# LEO_COTS_rev0.net
KiCad netlist of a schematic drawn in Altium Designer
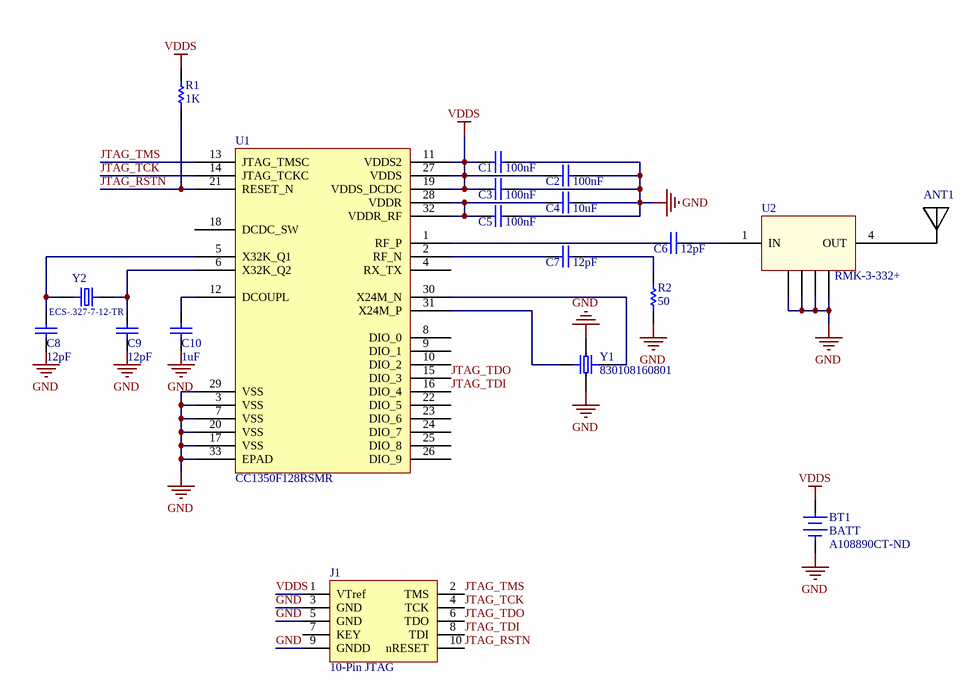
[diagram p0: LEO_COTS_rev0.SchDoc]

(export (version "E")
  (design (tool "Eeschema 10.0.6"))
  (components
    (comp (ref "ANT1") (value "ANT") (libsource (lib "LEO_COTS_components") (part "ANT")))
    (comp (ref "BT1")
      (value "BATT")
      (footprint "1318164-1")
      (fields (field (name "SUPPLIER PART NUMBER 1") "A108890CT-ND"))
      (libsource (lib "LEO_COTS_components") (part "BATT"))
    )
    (comp (ref "C1")
      (value "100nF")
      (footprint "CAPC0603X04N")
      (description "CAP CER 0201")
      (fields (field (name "Comment") "CAP_0201"))
      (libsource (lib "LEO_COTS_components") (part "CAP_0201"))
    )
    (comp (ref "C2")
      (value "100nF")
      (footprint "CAPC0603X04N")
      (description "CAP CER 0201")
      (fields (field (name "Comment") "CAP_0201"))
      (libsource (lib "LEO_COTS_components") (part "CAP_0201"))
    )
    (comp (ref "C3")
      (value "100nF")
      (footprint "CAPC0603X04N")
      (description "CAP CER 0201")
      (fields (field (name "Comment") "CAP_0201"))
      (libsource (lib "LEO_COTS_components") (part "CAP_0201"))
    )
    (comp (ref "C4")
      (value "10uF")
      (footprint "CAPC1608X05N")
      (description "CAP CER 0603")
      (fields (field (name "Comment") "CAP_0603"))
      (libsource (lib "LEO_COTS_components") (part "CAP_0603"))
    )
    (comp (ref "C5")
      (value "100nF")
      (footprint "CAPC0603X04N")
      (description "CAP CER 0201")
      (fields (field (name "Comment") "CAP_0201"))
      (libsource (lib "LEO_COTS_components") (part "CAP_0201"))
    )
    (comp (ref "C6")
      (value "12pF")
      (footprint "CAPC0603X04N")
      (description "CAP CER 0201")
      (fields (field (name "Comment") "CAP_0201"))
      (libsource (lib "LEO_COTS_components") (part "CAP_0201"))
    )
    (comp (ref "C7")
      (value "12pF")
      (footprint "CAPC0603X04N")
      (description "CAP CER 0201")
      (fields (field (name "Comment") "CAP_0201"))
      (libsource (lib "LEO_COTS_components") (part "CAP_0201"))
    )
    (comp (ref "C8")
      (value "12pF")
      (footprint "CAPC0603X04N")
      (description "CAP CER 0201")
      (fields (field (name "Comment") "CAP_0201"))
      (libsource (lib "LEO_COTS_components") (part "CAP_0201"))
    )
    (comp (ref "C9")
      (value "12pF")
      (footprint "CAPC0603X04N")
      (description "CAP CER 0201")
      (fields (field (name "Comment") "CAP_0201"))
      (libsource (lib "LEO_COTS_components") (part "CAP_0201"))
    )
    (comp (ref "C10")
      (value "1uF")
      (footprint "CAPC0603X04N")
      (description "CAP CER 0201")
      (fields (field (name "Comment") "CAP_0201"))
      (libsource (lib "LEO_COTS_components") (part "CAP_0201"))
    )
    (comp (ref "J1")
      (value "10-Pin JTAG")
      (footprint "FTSH-105-01-F-DV-007-K")
      (libsource (lib "LEO_COTS_components") (part "CM10"))
    )
    (comp (ref "R1")
      (value "1K")
      (footprint "CAPC0603X04N")
      (description "Semiconductor Resistor")
      (fields (field (name "Comment") "Res Semi") (field (name "PUBLISHER") "Altium Limited"))
      (libsource (lib "LEO_COTS_components") (part "Res Semi"))
    )
    (comp (ref "R2")
      (value "50")
      (footprint "CAPC0603X04N")
      (description "Semiconductor Resistor")
      (fields (field (name "Comment") "Res Semi") (field (name "PUBLISHER") "Altium Limited"))
      (libsource (lib "LEO_COTS_components") (part "Res Semi"))
    )
    (comp (ref "U1")
      (value "CC1350F128RSMR")
      (footprint "QFN40P400X400X100-33N")
      (description "Ultra-Low-Power Dual-Band Wireless MCU")
      (libsource (lib "LEO_COTS_components") (part "CC1350F128RSMR"))
    )
    (comp (ref "U2")
      (value "RMK-3-332+")
      (footprint "RMK-3-331+")
      (description "3x Frequency Multiplier")
      (libsource (lib "LEO_COTS_components") (part "RMK-3-332+"))
    )
    (comp (ref "Y1")
      (value "830108160801")
      (footprint "LFXTAL081608")
      (description "24 MHz crystal")
      (fields (field (name "MP") "ECS-.327-7-12-TR"))
      (libsource (lib "LEO_COTS_components") (part "830108160801"))
    )
    (comp (ref "Y2")
      (value "ECS-.327-7-12-TR")
      (footprint "XTAL_ECS-.327-7-12-TR")
      (description "32.768 kHz SMD Crystal")
      (libsource (lib "LEO_COTS_components") (part "ECS-.327-7-12-TR"))
    )
  )
  (nets
    (net (code "1") (name "/JTAG_RSTN") (class "Default")
      (node (ref "J1") (pin "10") (pinfunction "nRESET_10") (pintype "passive"))
      (node (ref "R1") (pin "1") (pinfunction "1_1") (pintype "passive"))
      (node (ref "U1") (pin "21") (pinfunction "RESET_N_21") (pintype "passive"))
    )
    (net (code "2") (name "/JTAG_TCK") (class "Default")
      (node (ref "J1") (pin "4") (pinfunction "TCK_4") (pintype "passive"))
      (node (ref "U1") (pin "14") (pinfunction "JTAG_TCKC_14") (pintype "passive"))
    )
    (net (code "3") (name "/JTAG_TDI") (class "Default")
      (node (ref "J1") (pin "8") (pinfunction "TDI_8") (pintype "passive"))
      (node (ref "U1") (pin "16") (pinfunction "DIO_4_16") (pintype "passive"))
    )
    (net (code "4") (name "/JTAG_TDO") (class "Default")
      (node (ref "J1") (pin "6") (pinfunction "TDO_6") (pintype "passive"))
      (node (ref "U1") (pin "15") (pinfunction "DIO_3_15") (pintype "passive"))
    )
    (net (code "5") (name "/JTAG_TMS") (class "Default")
      (node (ref "J1") (pin "2") (pinfunction "TMS_2") (pintype "passive"))
      (node (ref "U1") (pin "13") (pinfunction "JTAG_TMSC_13") (pintype "passive"))
    )
    (net (code "6") (name "GND") (class "Default")
      (node (ref "BT1") (pin "2") (pinfunction "-_2") (pintype "passive"))
      (node (ref "C1") (pin "1") (pinfunction "1_1") (pintype "passive"))
      (node (ref "C10") (pin "1") (pinfunction "1_1") (pintype "passive"))
      (node (ref "C2") (pin "1") (pinfunction "1_1") (pintype "passive"))
      (node (ref "C3") (pin "1") (pinfunction "1_1") (pintype "passive"))
      (node (ref "C4") (pin "2") (pinfunction "2_2") (pintype "passive"))
      (node (ref "C5") (pin "1") (pinfunction "1_1") (pintype "passive"))
      (node (ref "C8") (pin "1") (pinfunction "1_1") (pintype "passive"))
      (node (ref "C9") (pin "1") (pinfunction "1_1") (pintype "passive"))
      (node (ref "J1") (pin "3") (pinfunction "GND_3") (pintype "passive"))
      (node (ref "J1") (pin "5") (pinfunction "GND_5") (pintype "passive"))
      (node (ref "J1") (pin "9") (pinfunction "GNDD_9") (pintype "passive"))
      (node (ref "R2") (pin "1") (pinfunction "1_1") (pintype "passive"))
      (node (ref "U1") (pin "17") (pinfunction "VSS_17") (pintype "passive"))
      (node (ref "U1") (pin "20") (pinfunction "VSS_20") (pintype "passive"))
      (node (ref "U1") (pin "29") (pinfunction "VSS_29") (pintype "passive"))
      (node (ref "U1") (pin "3") (pinfunction "VSS_3") (pintype "passive"))
      (node (ref "U1") (pin "33") (pinfunction "EPAD_33") (pintype "passive"))
      (node (ref "U1") (pin "7") (pinfunction "VSS_7") (pintype "passive"))
      (node (ref "U2") (pin "2") (pinfunction "2_2") (pintype "passive"))
      (node (ref "U2") (pin "3") (pinfunction "3_3") (pintype "passive"))
      (node (ref "U2") (pin "5") (pinfunction "5_5") (pintype "passive"))
      (node (ref "U2") (pin "6") (pinfunction "6_6") (pintype "passive"))
      (node (ref "Y1") (pin "2") (pinfunction "2_2") (pintype "passive"))
      (node (ref "Y1") (pin "4") (pinfunction "4_4") (pintype "passive"))
    )
    (net (code "7") (name "Net-(C7-Pad1)") (class "Default")
      (node (ref "C7") (pin "1") (pinfunction "1_1") (pintype "passive"))
      (node (ref "R2") (pin "2") (pinfunction "2_2") (pintype "passive"))
    )
    (net (code "8") (name "Net-(U1-DCOUPL)") (class "Default")
      (node (ref "C10") (pin "2") (pinfunction "2_2") (pintype "passive"))
      (node (ref "U1") (pin "12") (pinfunction "DCOUPL_12") (pintype "passive"))
    )
    (net (code "9") (name "Net-(U1-RF_N)") (class "Default")
      (node (ref "C7") (pin "2") (pinfunction "2_2") (pintype "passive"))
      (node (ref "U1") (pin "2") (pinfunction "RF_N_2") (pintype "passive"))
    )
    (net (code "10") (name "Net-(U1-RF_P)") (class "Default")
      (node (ref "C6") (pin "2") (pinfunction "2_2") (pintype "passive"))
      (node (ref "U1") (pin "1") (pinfunction "RF_P_1") (pintype "passive"))
    )
    (net (code "11") (name "Net-(U1-VDDR)") (class "Default")
      (node (ref "C4") (pin "1") (pinfunction "1_1") (pintype "passive"))
      (node (ref "C5") (pin "2") (pinfunction "2_2") (pintype "passive"))
      (node (ref "U1") (pin "28") (pinfunction "VDDR_28") (pintype "passive"))
      (node (ref "U1") (pin "32") (pinfunction "VDDR_RF_32") (pintype "passive"))
    )
    (net (code "12") (name "Net-(U1-X24M_N)") (class "Default")
      (node (ref "U1") (pin "30") (pinfunction "X24M_N_30") (pintype "passive"))
      (node (ref "Y1") (pin "3") (pinfunction "3_3") (pintype "passive"))
    )
    (net (code "13") (name "Net-(U1-X24M_P)") (class "Default")
      (node (ref "U1") (pin "31") (pinfunction "X24M_P_31") (pintype "passive"))
      (node (ref "Y1") (pin "1") (pinfunction "1_1") (pintype "passive"))
    )
    (net (code "14") (name "Net-(U1-X32K_Q1)") (class "Default")
      (node (ref "C8") (pin "2") (pinfunction "2_2") (pintype "passive"))
      (node (ref "U1") (pin "5") (pinfunction "X32K_Q1_5") (pintype "passive"))
      (node (ref "Y2") (pin "1") (pinfunction "1_1") (pintype "passive"))
    )
    (net (code "15") (name "Net-(U1-X32K_Q2)") (class "Default")
      (node (ref "C9") (pin "2") (pinfunction "2_2") (pintype "passive"))
      (node (ref "U1") (pin "6") (pinfunction "X32K_Q2_6") (pintype "passive"))
      (node (ref "Y2") (pin "2") (pinfunction "2_2") (pintype "passive"))
    )
    (net (code "16") (name "Net-(U2-IN)") (class "Default")
      (node (ref "C6") (pin "1") (pinfunction "1_1") (pintype "passive"))
      (node (ref "U2") (pin "1") (pinfunction "IN_1") (pintype "passive"))
    )
    (net (code "17") (name "VDDS") (class "Default")
      (node (ref "BT1") (pin "1") (pinfunction "+_1") (pintype "passive"))
      (node (ref "C1") (pin "2") (pinfunction "2_2") (pintype "passive"))
      (node (ref "C2") (pin "2") (pinfunction "2_2") (pintype "passive"))
      (node (ref "C3") (pin "2") (pinfunction "2_2") (pintype "passive"))
      (node (ref "J1") (pin "1") (pinfunction "VTref_1") (pintype "passive"))
      (node (ref "R1") (pin "2") (pinfunction "2_2") (pintype "passive"))
      (node (ref "U1") (pin "11") (pinfunction "VDDS2_11") (pintype "passive"))
      (node (ref "U1") (pin "19") (pinfunction "VDDS_DCDC_19") (pintype "passive"))
      (node (ref "U1") (pin "27") (pinfunction "VDDS_27") (pintype "passive"))
    )
    (net (code "18") (name "unconnected-(J1-KEY-Pad7)") (class "Default")
      (node (ref "J1") (pin "7") (pinfunction "KEY_7") (pintype "passive"))
    )
    (net (code "19") (name "unconnected-(U1-DCDC_SW-Pad18)") (class "Default")
      (node (ref "U1") (pin "18") (pinfunction "DCDC_SW_18") (pintype "passive"))
    )
    (net (code "20") (name "unconnected-(U1-DIO_0-Pad8)") (class "Default")
      (node (ref "U1") (pin "8") (pinfunction "DIO_0_8") (pintype "passive"))
    )
    (net (code "21") (name "unconnected-(U1-DIO_1-Pad9)") (class "Default")
      (node (ref "U1") (pin "9") (pinfunction "DIO_1_9") (pintype "passive"))
    )
    (net (code "22") (name "unconnected-(U1-DIO_2-Pad10)") (class "Default")
      (node (ref "U1") (pin "10") (pinfunction "DIO_2_10") (pintype "passive"))
    )
    (net (code "23") (name "unconnected-(U1-DIO_5-Pad22)") (class "Default")
      (node (ref "U1") (pin "22") (pinfunction "DIO_5_22") (pintype "passive"))
    )
    (net (code "24") (name "unconnected-(U1-DIO_6-Pad23)") (class "Default")
      (node (ref "U1") (pin "23") (pinfunction "DIO_6_23") (pintype "passive"))
    )
    (net (code "25") (name "unconnected-(U1-DIO_7-Pad24)") (class "Default")
      (node (ref "U1") (pin "24") (pinfunction "DIO_7_24") (pintype "passive"))
    )
    (net (code "26") (name "unconnected-(U1-DIO_8-Pad25)") (class "Default")
      (node (ref "U1") (pin "25") (pinfunction "DIO_8_25") (pintype "passive"))
    )
    (net (code "27") (name "unconnected-(U1-DIO_9-Pad26)") (class "Default")
      (node (ref "U1") (pin "26") (pinfunction "DIO_9_26") (pintype "passive"))
    )
    (net (code "28") (name "unconnected-(U1-RX_TX-Pad4)") (class "Default")
      (node (ref "U1") (pin "4") (pinfunction "RX_TX_4") (pintype "passive"))
    )
    (net (code "29") (name "unconnected-(U2-OUT-Pad4)") (class "Default")
      (node (ref "U2") (pin "4") (pinfunction "OUT_4") (pintype "passive"))
    )
  )
)
